# power.net
KiCad netlist of a schematic drawn in Altium Designer
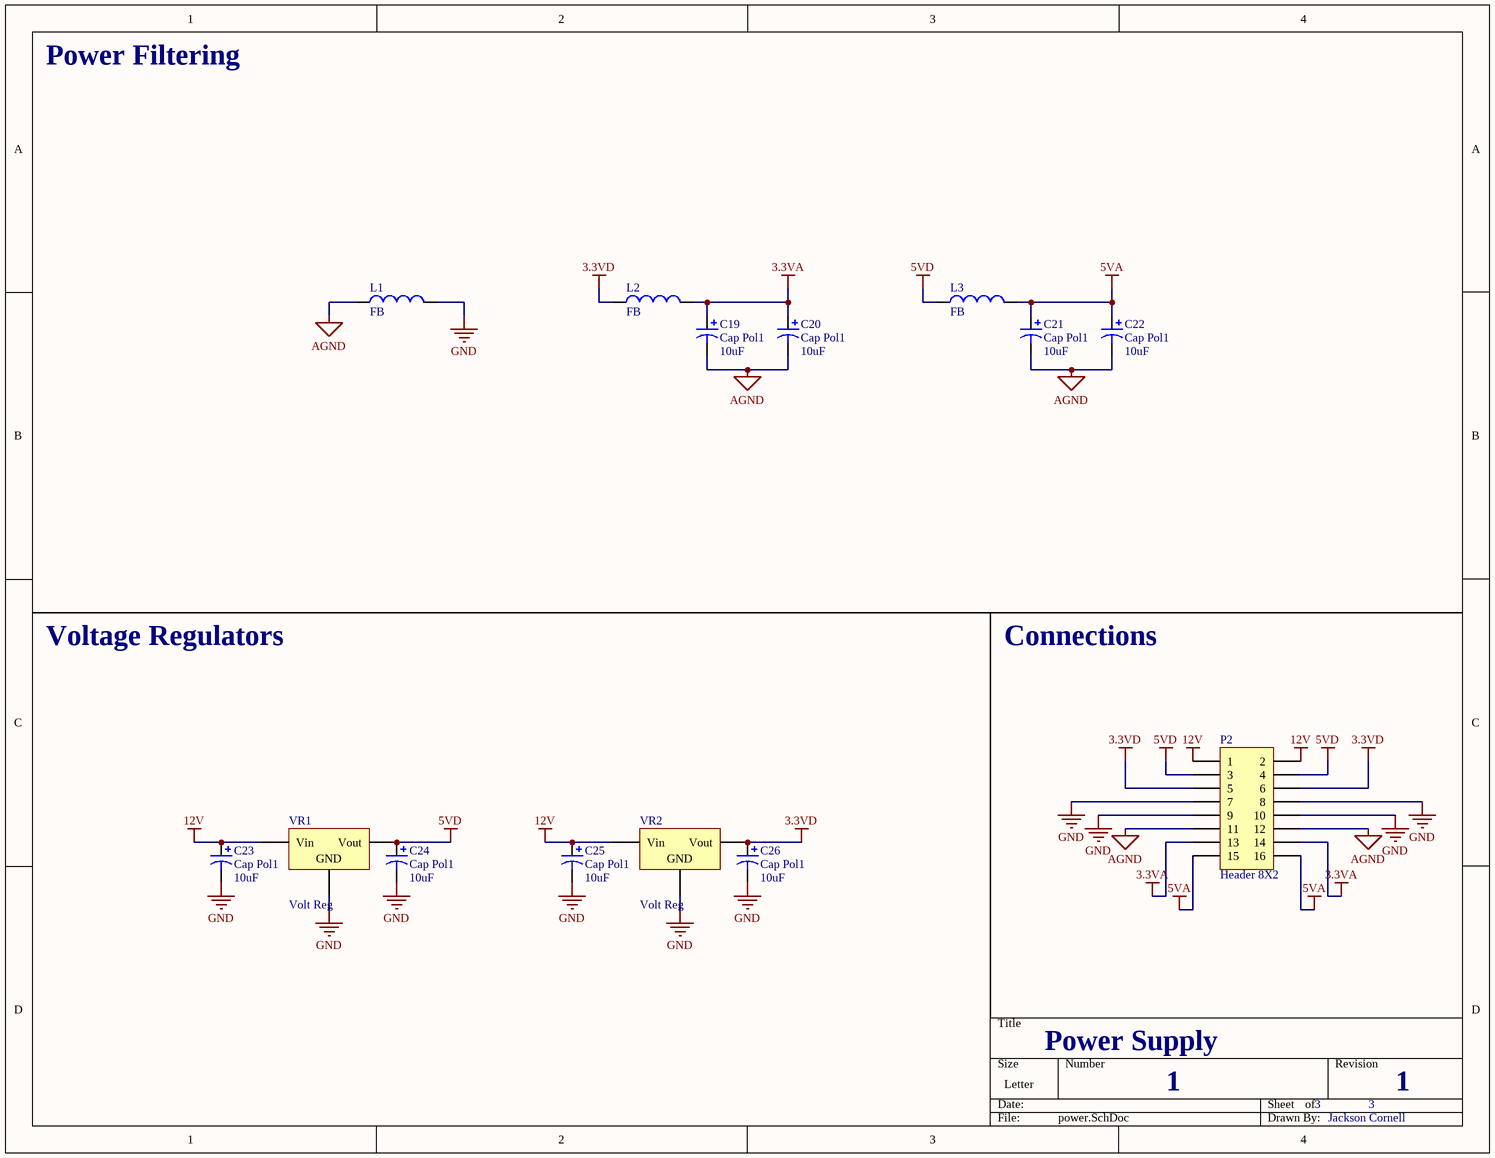
[diagram p0: power.SchDoc]

(export (version "E")
  (design (tool "Eeschema 10.0.6"))
  (components
    (comp (ref "C19")
      (value "Cap Pol1")
      (footprint "RB7.6-15")
      (description "Polarized Capacitor (Radial)")
      (fields (field (name "ALTIUM_VALUE") "10uF") (field (name "PUBLISHER") "Altium Limited"))
      (libsource (lib "Miscellaneous Devices") (part "Cap Pol1"))
    )
    (comp (ref "C20")
      (value "Cap Pol1")
      (footprint "RB7.6-15")
      (description "Polarized Capacitor (Radial)")
      (fields (field (name "ALTIUM_VALUE") "10uF") (field (name "PUBLISHER") "Altium Limited"))
      (libsource (lib "Miscellaneous Devices") (part "Cap Pol1"))
    )
    (comp (ref "C21")
      (value "Cap Pol1")
      (footprint "RB7.6-15")
      (description "Polarized Capacitor (Radial)")
      (fields (field (name "ALTIUM_VALUE") "10uF") (field (name "PUBLISHER") "Altium Limited"))
      (libsource (lib "Miscellaneous Devices") (part "Cap Pol1"))
    )
    (comp (ref "C22")
      (value "Cap Pol1")
      (footprint "RB7.6-15")
      (description "Polarized Capacitor (Radial)")
      (fields (field (name "ALTIUM_VALUE") "10uF") (field (name "PUBLISHER") "Altium Limited"))
      (libsource (lib "Miscellaneous Devices") (part "Cap Pol1"))
    )
    (comp (ref "C23")
      (value "Cap Pol1")
      (footprint "RB7.6-15")
      (description "Polarized Capacitor (Radial)")
      (fields (field (name "ALTIUM_VALUE") "10uF") (field (name "PUBLISHER") "Altium Limited"))
      (libsource (lib "Miscellaneous Devices") (part "Cap Pol1"))
    )
    (comp (ref "C24")
      (value "Cap Pol1")
      (footprint "RB7.6-15")
      (description "Polarized Capacitor (Radial)")
      (fields (field (name "ALTIUM_VALUE") "10uF") (field (name "PUBLISHER") "Altium Limited"))
      (libsource (lib "Miscellaneous Devices") (part "Cap Pol1"))
    )
    (comp (ref "C25")
      (value "Cap Pol1")
      (footprint "RB7.6-15")
      (description "Polarized Capacitor (Radial)")
      (fields (field (name "ALTIUM_VALUE") "10uF") (field (name "PUBLISHER") "Altium Limited"))
      (libsource (lib "Miscellaneous Devices") (part "Cap Pol1"))
    )
    (comp (ref "C26")
      (value "Cap Pol1")
      (footprint "RB7.6-15")
      (description "Polarized Capacitor (Radial)")
      (fields (field (name "ALTIUM_VALUE") "10uF") (field (name "PUBLISHER") "Altium Limited"))
      (libsource (lib "Miscellaneous Devices") (part "Cap Pol1"))
    )
    (comp (ref "L1")
      (value "FB")
      (footprint "0402-A")
      (description "Inductor")
      (fields (field (name "PUBLISHER") "Altium Limited"))
      (libsource (lib "Miscellaneous Devices") (part "Inductor"))
    )
    (comp (ref "L2")
      (value "FB")
      (footprint "0402-A")
      (description "Inductor")
      (fields (field (name "PUBLISHER") "Altium Limited"))
      (libsource (lib "Miscellaneous Devices") (part "Inductor"))
    )
    (comp (ref "L3")
      (value "FB")
      (footprint "0402-A")
      (description "Inductor")
      (fields (field (name "PUBLISHER") "Altium Limited"))
      (libsource (lib "Miscellaneous Devices") (part "Inductor"))
    )
    (comp (ref "P2")
      (value "Header 8X2")
      (footprint "HDR2X8")
      (description "Header, 8-Pin, Dual row")
      (fields (field (name "PUBLISHER") "Altium Limited"))
      (libsource (lib "Miscellaneous Connectors") (part "Header 8X2"))
    )
    (comp (ref "VR1")
      (value "Volt Reg")
      (footprint "D2PAK_N")
      (description "Voltage Regulator")
      (fields (field (name "PUBLISHER") "Altium Limited"))
      (libsource (lib "Miscellaneous Devices") (part "Volt Reg"))
    )
    (comp (ref "VR2")
      (value "Volt Reg")
      (footprint "D2PAK_N")
      (description "Voltage Regulator")
      (fields (field (name "PUBLISHER") "Altium Limited"))
      (libsource (lib "Miscellaneous Devices") (part "Volt Reg"))
    )
  )
  (nets
    (net (code "1") (name "3.3VA") (class "Default")
      (node (ref "C19") (pin "1") (pinfunction "1_1") (pintype "passive"))
      (node (ref "C20") (pin "1") (pinfunction "1_1") (pintype "passive"))
      (node (ref "L2") (pin "2") (pinfunction "2_2") (pintype "passive"))
      (node (ref "P2") (pin "13") (pinfunction "13_13") (pintype "passive"))
      (node (ref "P2") (pin "14") (pinfunction "14_14") (pintype "passive"))
    )
    (net (code "2") (name "3.3VD") (class "Default")
      (node (ref "C26") (pin "1") (pinfunction "1_1") (pintype "passive"))
      (node (ref "L2") (pin "1") (pinfunction "1_1") (pintype "passive"))
      (node (ref "P2") (pin "5") (pinfunction "5_5") (pintype "passive"))
      (node (ref "P2") (pin "6") (pinfunction "6_6") (pintype "passive"))
      (node (ref "VR2") (pin "3") (pinfunction "Vout_3") (pintype "passive"))
    )
    (net (code "3") (name "5VA") (class "Default")
      (node (ref "C21") (pin "1") (pinfunction "1_1") (pintype "passive"))
      (node (ref "C22") (pin "1") (pinfunction "1_1") (pintype "passive"))
      (node (ref "L3") (pin "2") (pinfunction "2_2") (pintype "passive"))
      (node (ref "P2") (pin "15") (pinfunction "15_15") (pintype "passive"))
      (node (ref "P2") (pin "16") (pinfunction "16_16") (pintype "passive"))
    )
    (net (code "4") (name "5VD") (class "Default")
      (node (ref "C24") (pin "1") (pinfunction "1_1") (pintype "passive"))
      (node (ref "L3") (pin "1") (pinfunction "1_1") (pintype "passive"))
      (node (ref "P2") (pin "3") (pinfunction "3_3") (pintype "passive"))
      (node (ref "P2") (pin "4") (pinfunction "4_4") (pintype "passive"))
      (node (ref "VR1") (pin "3") (pinfunction "Vout_3") (pintype "passive"))
    )
    (net (code "5") (name "12V") (class "Default")
      (node (ref "C23") (pin "1") (pinfunction "1_1") (pintype "passive"))
      (node (ref "C25") (pin "1") (pinfunction "1_1") (pintype "passive"))
      (node (ref "P2") (pin "1") (pinfunction "1_1") (pintype "passive"))
      (node (ref "P2") (pin "2") (pinfunction "2_2") (pintype "passive"))
      (node (ref "VR1") (pin "1") (pinfunction "Vin_1") (pintype "passive"))
      (node (ref "VR2") (pin "1") (pinfunction "Vin_1") (pintype "passive"))
    )
    (net (code "6") (name "AGND") (class "Default")
      (node (ref "C19") (pin "2") (pinfunction "2_2") (pintype "passive"))
      (node (ref "C20") (pin "2") (pinfunction "2_2") (pintype "passive"))
      (node (ref "C21") (pin "2") (pinfunction "2_2") (pintype "passive"))
      (node (ref "C22") (pin "2") (pinfunction "2_2") (pintype "passive"))
      (node (ref "L1") (pin "1") (pinfunction "1_1") (pintype "passive"))
      (node (ref "P2") (pin "11") (pinfunction "11_11") (pintype "passive"))
      (node (ref "P2") (pin "12") (pinfunction "12_12") (pintype "passive"))
    )
    (net (code "7") (name "GND") (class "Default")
      (node (ref "C23") (pin "2") (pinfunction "2_2") (pintype "passive"))
      (node (ref "C24") (pin "2") (pinfunction "2_2") (pintype "passive"))
      (node (ref "C25") (pin "2") (pinfunction "2_2") (pintype "passive"))
      (node (ref "C26") (pin "2") (pinfunction "2_2") (pintype "passive"))
      (node (ref "L1") (pin "2") (pinfunction "2_2") (pintype "passive"))
      (node (ref "P2") (pin "10") (pinfunction "10_10") (pintype "passive"))
      (node (ref "P2") (pin "7") (pinfunction "7_7") (pintype "passive"))
      (node (ref "P2") (pin "8") (pinfunction "8_8") (pintype "passive"))
      (node (ref "P2") (pin "9") (pinfunction "9_9") (pintype "passive"))
      (node (ref "VR1") (pin "2") (pinfunction "GND_2") (pintype "passive"))
      (node (ref "VR2") (pin "2") (pinfunction "GND_2") (pintype "passive"))
    )
  )
)
